# driver_board_v1.net
KiCad netlist of a schematic drawn in EAGLE
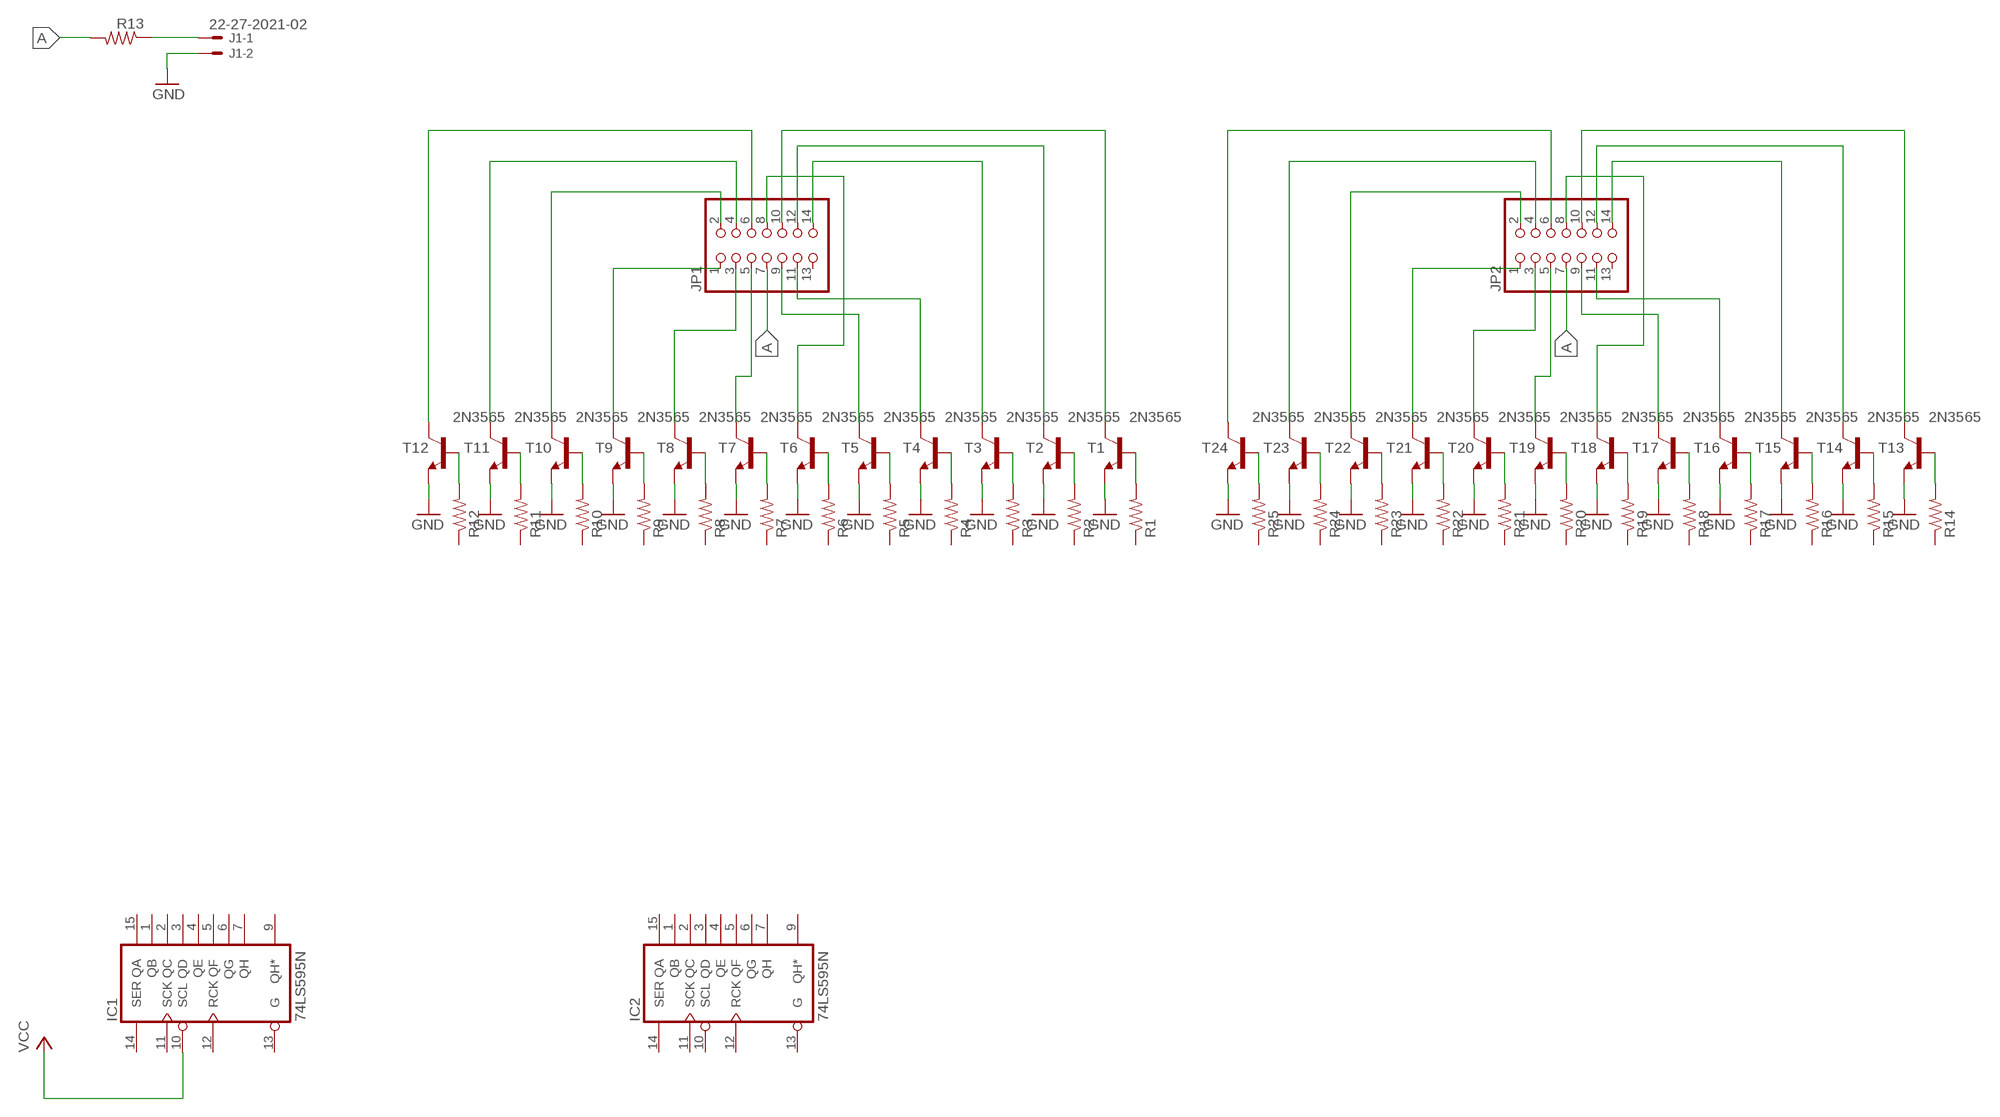
[diagram p0: schematic, sheet 1]

(export (version "E")
  (design (tool "Eeschema 10.0.6"))
  (components
    (comp (ref "IC1")
      (value "74LS595N")
      (footprint "eagle-import:DIL16")
      (libsource (lib "eagle-import") (part "74595NLS"))
    )
    (comp (ref "IC2")
      (value "74LS595N")
      (footprint "eagle-import:DIL16")
      (libsource (lib "eagle-import") (part "74595NLS"))
    )
    (comp (ref "J1")
      (value "22-27-2021-02")
      (footprint "eagle-import:6410-02")
      (libsource (lib "eagle-import") (part "22-?-0227-2021"))
    )
    (comp (ref "JP1")
      (value "PINHD-2X7")
      (footprint "eagle-import:2X07")
      (libsource (lib "eagle-import") (part "PINHD-2X7"))
    )
    (comp (ref "JP2")
      (value "PINHD-2X7")
      (footprint "eagle-import:2X07")
      (libsource (lib "eagle-import") (part "PINHD-2X7"))
    )
    (comp (ref "R1")
      (value "R-US_0204/7")
      (footprint "eagle-import:0204_7")
      (libsource (lib "eagle-import") (part "R-US_0204/7"))
    )
    (comp (ref "R2")
      (value "R-US_0204/7")
      (footprint "eagle-import:0204_7")
      (libsource (lib "eagle-import") (part "R-US_0204/7"))
    )
    (comp (ref "R3")
      (value "R-US_0204/7")
      (footprint "eagle-import:0204_7")
      (libsource (lib "eagle-import") (part "R-US_0204/7"))
    )
    (comp (ref "R4")
      (value "R-US_0204/7")
      (footprint "eagle-import:0204_7")
      (libsource (lib "eagle-import") (part "R-US_0204/7"))
    )
    (comp (ref "R5")
      (value "R-US_0204/7")
      (footprint "eagle-import:0204_7")
      (libsource (lib "eagle-import") (part "R-US_0204/7"))
    )
    (comp (ref "R6")
      (value "R-US_0204/7")
      (footprint "eagle-import:0204_7")
      (libsource (lib "eagle-import") (part "R-US_0204/7"))
    )
    (comp (ref "R7")
      (value "R-US_0204/7")
      (footprint "eagle-import:0204_7")
      (libsource (lib "eagle-import") (part "R-US_0204/7"))
    )
    (comp (ref "R8")
      (value "R-US_0204/7")
      (footprint "eagle-import:0204_7")
      (libsource (lib "eagle-import") (part "R-US_0204/7"))
    )
    (comp (ref "R9")
      (value "R-US_0204/7")
      (footprint "eagle-import:0204_7")
      (libsource (lib "eagle-import") (part "R-US_0204/7"))
    )
    (comp (ref "R10")
      (value "R-US_0204/7")
      (footprint "eagle-import:0204_7")
      (libsource (lib "eagle-import") (part "R-US_0204/7"))
    )
    (comp (ref "R11")
      (value "R-US_0204/7")
      (footprint "eagle-import:0204_7")
      (libsource (lib "eagle-import") (part "R-US_0204/7"))
    )
    (comp (ref "R12")
      (value "R-US_0204/7")
      (footprint "eagle-import:0204_7")
      (libsource (lib "eagle-import") (part "R-US_0204/7"))
    )
    (comp (ref "R13")
      (value "R-US_0204/7")
      (footprint "eagle-import:0204_7")
      (libsource (lib "eagle-import") (part "R-US_0204/7"))
    )
    (comp (ref "R14")
      (value "R-US_0204/7")
      (footprint "eagle-import:0204_7")
      (libsource (lib "eagle-import") (part "R-US_0204/7"))
    )
    (comp (ref "R15")
      (value "R-US_0204/7")
      (footprint "eagle-import:0204_7")
      (libsource (lib "eagle-import") (part "R-US_0204/7"))
    )
    (comp (ref "R16")
      (value "R-US_0204/7")
      (footprint "eagle-import:0204_7")
      (libsource (lib "eagle-import") (part "R-US_0204/7"))
    )
    (comp (ref "R17")
      (value "R-US_0204/7")
      (footprint "eagle-import:0204_7")
      (libsource (lib "eagle-import") (part "R-US_0204/7"))
    )
    (comp (ref "R18")
      (value "R-US_0204/7")
      (footprint "eagle-import:0204_7")
      (libsource (lib "eagle-import") (part "R-US_0204/7"))
    )
    (comp (ref "R19")
      (value "R-US_0204/7")
      (footprint "eagle-import:0204_7")
      (libsource (lib "eagle-import") (part "R-US_0204/7"))
    )
    (comp (ref "R20")
      (value "R-US_0204/7")
      (footprint "eagle-import:0204_7")
      (libsource (lib "eagle-import") (part "R-US_0204/7"))
    )
    (comp (ref "R21")
      (value "R-US_0204/7")
      (footprint "eagle-import:0204_7")
      (libsource (lib "eagle-import") (part "R-US_0204/7"))
    )
    (comp (ref "R22")
      (value "R-US_0204/7")
      (footprint "eagle-import:0204_7")
      (libsource (lib "eagle-import") (part "R-US_0204/7"))
    )
    (comp (ref "R23")
      (value "R-US_0204/7")
      (footprint "eagle-import:0204_7")
      (libsource (lib "eagle-import") (part "R-US_0204/7"))
    )
    (comp (ref "R24")
      (value "R-US_0204/7")
      (footprint "eagle-import:0204_7")
      (libsource (lib "eagle-import") (part "R-US_0204/7"))
    )
    (comp (ref "R25")
      (value "R-US_0204/7")
      (footprint "eagle-import:0204_7")
      (libsource (lib "eagle-import") (part "R-US_0204/7"))
    )
    (comp (ref "T1")
      (value "2N3565")
      (footprint "eagle-import:TO92")
      (libsource (lib "eagle-import") (part "2N3565"))
    )
    (comp (ref "T2")
      (value "2N3565")
      (footprint "eagle-import:TO92")
      (libsource (lib "eagle-import") (part "2N3565"))
    )
    (comp (ref "T3")
      (value "2N3565")
      (footprint "eagle-import:TO92")
      (libsource (lib "eagle-import") (part "2N3565"))
    )
    (comp (ref "T4")
      (value "2N3565")
      (footprint "eagle-import:TO92")
      (libsource (lib "eagle-import") (part "2N3565"))
    )
    (comp (ref "T5")
      (value "2N3565")
      (footprint "eagle-import:TO92")
      (libsource (lib "eagle-import") (part "2N3565"))
    )
    (comp (ref "T6")
      (value "2N3565")
      (footprint "eagle-import:TO92")
      (libsource (lib "eagle-import") (part "2N3565"))
    )
    (comp (ref "T7")
      (value "2N3565")
      (footprint "eagle-import:TO92")
      (libsource (lib "eagle-import") (part "2N3565"))
    )
    (comp (ref "T8")
      (value "2N3565")
      (footprint "eagle-import:TO92")
      (libsource (lib "eagle-import") (part "2N3565"))
    )
    (comp (ref "T9")
      (value "2N3565")
      (footprint "eagle-import:TO92")
      (libsource (lib "eagle-import") (part "2N3565"))
    )
    (comp (ref "T10")
      (value "2N3565")
      (footprint "eagle-import:TO92")
      (libsource (lib "eagle-import") (part "2N3565"))
    )
    (comp (ref "T11")
      (value "2N3565")
      (footprint "eagle-import:TO92")
      (libsource (lib "eagle-import") (part "2N3565"))
    )
    (comp (ref "T12")
      (value "2N3565")
      (footprint "eagle-import:TO92")
      (libsource (lib "eagle-import") (part "2N3565"))
    )
    (comp (ref "T13")
      (value "2N3565")
      (footprint "eagle-import:TO92")
      (libsource (lib "eagle-import") (part "2N3565"))
    )
    (comp (ref "T14")
      (value "2N3565")
      (footprint "eagle-import:TO92")
      (libsource (lib "eagle-import") (part "2N3565"))
    )
    (comp (ref "T15")
      (value "2N3565")
      (footprint "eagle-import:TO92")
      (libsource (lib "eagle-import") (part "2N3565"))
    )
    (comp (ref "T16")
      (value "2N3565")
      (footprint "eagle-import:TO92")
      (libsource (lib "eagle-import") (part "2N3565"))
    )
    (comp (ref "T17")
      (value "2N3565")
      (footprint "eagle-import:TO92")
      (libsource (lib "eagle-import") (part "2N3565"))
    )
    (comp (ref "T18")
      (value "2N3565")
      (footprint "eagle-import:TO92")
      (libsource (lib "eagle-import") (part "2N3565"))
    )
    (comp (ref "T19")
      (value "2N3565")
      (footprint "eagle-import:TO92")
      (libsource (lib "eagle-import") (part "2N3565"))
    )
    (comp (ref "T20")
      (value "2N3565")
      (footprint "eagle-import:TO92")
      (libsource (lib "eagle-import") (part "2N3565"))
    )
    (comp (ref "T21")
      (value "2N3565")
      (footprint "eagle-import:TO92")
      (libsource (lib "eagle-import") (part "2N3565"))
    )
    (comp (ref "T22")
      (value "2N3565")
      (footprint "eagle-import:TO92")
      (libsource (lib "eagle-import") (part "2N3565"))
    )
    (comp (ref "T23")
      (value "2N3565")
      (footprint "eagle-import:TO92")
      (libsource (lib "eagle-import") (part "2N3565"))
    )
    (comp (ref "T24")
      (value "2N3565")
      (footprint "eagle-import:TO92")
      (libsource (lib "eagle-import") (part "2N3565"))
    )
  )
  (nets
    (net (code "1") (name "A") (class "Default")
      (node (ref "JP1") (pin "7") (pinfunction "7_7") (pintype "passive"))
      (node (ref "JP2") (pin "7") (pinfunction "7_7") (pintype "passive"))
      (node (ref "R13") (pin "2") (pinfunction "2_2") (pintype "passive"))
    )
    (net (code "2") (name "GND") (class "Default")
      (node (ref "J1") (pin "2") (pinfunction "S_2") (pintype "passive"))
      (node (ref "T1") (pin "3") (pinfunction "E_3") (pintype "passive"))
      (node (ref "T10") (pin "3") (pinfunction "E_3") (pintype "passive"))
      (node (ref "T11") (pin "3") (pinfunction "E_3") (pintype "passive"))
      (node (ref "T12") (pin "3") (pinfunction "E_3") (pintype "passive"))
      (node (ref "T13") (pin "3") (pinfunction "E_3") (pintype "passive"))
      (node (ref "T14") (pin "3") (pinfunction "E_3") (pintype "passive"))
      (node (ref "T15") (pin "3") (pinfunction "E_3") (pintype "passive"))
      (node (ref "T16") (pin "3") (pinfunction "E_3") (pintype "passive"))
      (node (ref "T17") (pin "3") (pinfunction "E_3") (pintype "passive"))
      (node (ref "T18") (pin "3") (pinfunction "E_3") (pintype "passive"))
      (node (ref "T19") (pin "3") (pinfunction "E_3") (pintype "passive"))
      (node (ref "T2") (pin "3") (pinfunction "E_3") (pintype "passive"))
      (node (ref "T20") (pin "3") (pinfunction "E_3") (pintype "passive"))
      (node (ref "T21") (pin "3") (pinfunction "E_3") (pintype "passive"))
      (node (ref "T22") (pin "3") (pinfunction "E_3") (pintype "passive"))
      (node (ref "T23") (pin "3") (pinfunction "E_3") (pintype "passive"))
      (node (ref "T24") (pin "3") (pinfunction "E_3") (pintype "passive"))
      (node (ref "T3") (pin "3") (pinfunction "E_3") (pintype "passive"))
      (node (ref "T4") (pin "3") (pinfunction "E_3") (pintype "passive"))
      (node (ref "T5") (pin "3") (pinfunction "E_3") (pintype "passive"))
      (node (ref "T6") (pin "3") (pinfunction "E_3") (pintype "passive"))
      (node (ref "T7") (pin "3") (pinfunction "E_3") (pintype "passive"))
      (node (ref "T8") (pin "3") (pinfunction "E_3") (pintype "passive"))
      (node (ref "T9") (pin "3") (pinfunction "E_3") (pintype "passive"))
    )
    (net (code "3") (name "Net-(J1A-S)") (class "Default")
      (node (ref "J1") (pin "1") (pinfunction "S_1") (pintype "passive"))
      (node (ref "R13") (pin "1") (pinfunction "1_1") (pintype "passive"))
    )
    (net (code "4") (name "Net-(T1-B)") (class "Default")
      (node (ref "R1") (pin "2") (pinfunction "2_2") (pintype "passive"))
      (node (ref "T1") (pin "2") (pinfunction "B_2") (pintype "passive"))
    )
    (net (code "5") (name "Net-(T1-C)") (class "Default")
      (node (ref "JP1") (pin "10") (pinfunction "10_10") (pintype "passive"))
      (node (ref "T1") (pin "1") (pinfunction "C_1") (pintype "passive"))
    )
    (net (code "6") (name "Net-(T2-B)") (class "Default")
      (node (ref "R2") (pin "2") (pinfunction "2_2") (pintype "passive"))
      (node (ref "T2") (pin "2") (pinfunction "B_2") (pintype "passive"))
    )
    (net (code "7") (name "Net-(T2-C)") (class "Default")
      (node (ref "JP1") (pin "12") (pinfunction "12_12") (pintype "passive"))
      (node (ref "T2") (pin "1") (pinfunction "C_1") (pintype "passive"))
    )
    (net (code "8") (name "Net-(T3-B)") (class "Default")
      (node (ref "R3") (pin "2") (pinfunction "2_2") (pintype "passive"))
      (node (ref "T3") (pin "2") (pinfunction "B_2") (pintype "passive"))
    )
    (net (code "9") (name "Net-(T3-C)") (class "Default")
      (node (ref "JP1") (pin "14") (pinfunction "14_14") (pintype "passive"))
      (node (ref "T3") (pin "1") (pinfunction "C_1") (pintype "passive"))
    )
    (net (code "10") (name "Net-(T4-B)") (class "Default")
      (node (ref "R4") (pin "2") (pinfunction "2_2") (pintype "passive"))
      (node (ref "T4") (pin "2") (pinfunction "B_2") (pintype "passive"))
    )
    (net (code "11") (name "Net-(T4-C)") (class "Default")
      (node (ref "JP1") (pin "11") (pinfunction "11_11") (pintype "passive"))
      (node (ref "T4") (pin "1") (pinfunction "C_1") (pintype "passive"))
    )
    (net (code "12") (name "Net-(T5-B)") (class "Default")
      (node (ref "R5") (pin "2") (pinfunction "2_2") (pintype "passive"))
      (node (ref "T5") (pin "2") (pinfunction "B_2") (pintype "passive"))
    )
    (net (code "13") (name "Net-(T5-C)") (class "Default")
      (node (ref "JP1") (pin "9") (pinfunction "9_9") (pintype "passive"))
      (node (ref "T5") (pin "1") (pinfunction "C_1") (pintype "passive"))
    )
    (net (code "14") (name "Net-(T6-B)") (class "Default")
      (node (ref "R6") (pin "2") (pinfunction "2_2") (pintype "passive"))
      (node (ref "T6") (pin "2") (pinfunction "B_2") (pintype "passive"))
    )
    (net (code "15") (name "Net-(T6-C)") (class "Default")
      (node (ref "JP1") (pin "8") (pinfunction "8_8") (pintype "passive"))
      (node (ref "T6") (pin "1") (pinfunction "C_1") (pintype "passive"))
    )
    (net (code "16") (name "Net-(T7-B)") (class "Default")
      (node (ref "R7") (pin "2") (pinfunction "2_2") (pintype "passive"))
      (node (ref "T7") (pin "2") (pinfunction "B_2") (pintype "passive"))
    )
    (net (code "17") (name "Net-(T7-C)") (class "Default")
      (node (ref "JP1") (pin "5") (pinfunction "5_5") (pintype "passive"))
      (node (ref "T7") (pin "1") (pinfunction "C_1") (pintype "passive"))
    )
    (net (code "18") (name "Net-(T8-B)") (class "Default")
      (node (ref "R8") (pin "2") (pinfunction "2_2") (pintype "passive"))
      (node (ref "T8") (pin "2") (pinfunction "B_2") (pintype "passive"))
    )
    (net (code "19") (name "Net-(T8-C)") (class "Default")
      (node (ref "JP1") (pin "3") (pinfunction "3_3") (pintype "passive"))
      (node (ref "T8") (pin "1") (pinfunction "C_1") (pintype "passive"))
    )
    (net (code "20") (name "Net-(T9-B)") (class "Default")
      (node (ref "R9") (pin "2") (pinfunction "2_2") (pintype "passive"))
      (node (ref "T9") (pin "2") (pinfunction "B_2") (pintype "passive"))
    )
    (net (code "21") (name "Net-(T9-C)") (class "Default")
      (node (ref "JP1") (pin "1") (pinfunction "1_1") (pintype "passive"))
      (node (ref "T9") (pin "1") (pinfunction "C_1") (pintype "passive"))
    )
    (net (code "22") (name "Net-(T10-B)") (class "Default")
      (node (ref "R10") (pin "2") (pinfunction "2_2") (pintype "passive"))
      (node (ref "T10") (pin "2") (pinfunction "B_2") (pintype "passive"))
    )
    (net (code "23") (name "Net-(T10-C)") (class "Default")
      (node (ref "JP1") (pin "2") (pinfunction "2_2") (pintype "passive"))
      (node (ref "T10") (pin "1") (pinfunction "C_1") (pintype "passive"))
    )
    (net (code "24") (name "Net-(T11-B)") (class "Default")
      (node (ref "R11") (pin "2") (pinfunction "2_2") (pintype "passive"))
      (node (ref "T11") (pin "2") (pinfunction "B_2") (pintype "passive"))
    )
    (net (code "25") (name "Net-(T11-C)") (class "Default")
      (node (ref "JP1") (pin "4") (pinfunction "4_4") (pintype "passive"))
      (node (ref "T11") (pin "1") (pinfunction "C_1") (pintype "passive"))
    )
    (net (code "26") (name "Net-(T12-B)") (class "Default")
      (node (ref "R12") (pin "2") (pinfunction "2_2") (pintype "passive"))
      (node (ref "T12") (pin "2") (pinfunction "B_2") (pintype "passive"))
    )
    (net (code "27") (name "Net-(T12-C)") (class "Default")
      (node (ref "JP1") (pin "6") (pinfunction "6_6") (pintype "passive"))
      (node (ref "T12") (pin "1") (pinfunction "C_1") (pintype "passive"))
    )
    (net (code "28") (name "Net-(T13-B)") (class "Default")
      (node (ref "R14") (pin "2") (pinfunction "2_2") (pintype "passive"))
      (node (ref "T13") (pin "2") (pinfunction "B_2") (pintype "passive"))
    )
    (net (code "29") (name "Net-(T13-C)") (class "Default")
      (node (ref "JP2") (pin "10") (pinfunction "10_10") (pintype "passive"))
      (node (ref "T13") (pin "1") (pinfunction "C_1") (pintype "passive"))
    )
    (net (code "30") (name "Net-(T14-B)") (class "Default")
      (node (ref "R15") (pin "2") (pinfunction "2_2") (pintype "passive"))
      (node (ref "T14") (pin "2") (pinfunction "B_2") (pintype "passive"))
    )
    (net (code "31") (name "Net-(T14-C)") (class "Default")
      (node (ref "JP2") (pin "12") (pinfunction "12_12") (pintype "passive"))
      (node (ref "T14") (pin "1") (pinfunction "C_1") (pintype "passive"))
    )
    (net (code "32") (name "Net-(T15-B)") (class "Default")
      (node (ref "R16") (pin "2") (pinfunction "2_2") (pintype "passive"))
      (node (ref "T15") (pin "2") (pinfunction "B_2") (pintype "passive"))
    )
    (net (code "33") (name "Net-(T15-C)") (class "Default")
      (node (ref "JP2") (pin "14") (pinfunction "14_14") (pintype "passive"))
      (node (ref "T15") (pin "1") (pinfunction "C_1") (pintype "passive"))
    )
    (net (code "34") (name "Net-(T16-B)") (class "Default")
      (node (ref "R17") (pin "2") (pinfunction "2_2") (pintype "passive"))
      (node (ref "T16") (pin "2") (pinfunction "B_2") (pintype "passive"))
    )
    (net (code "35") (name "Net-(T16-C)") (class "Default")
      (node (ref "JP2") (pin "11") (pinfunction "11_11") (pintype "passive"))
      (node (ref "T16") (pin "1") (pinfunction "C_1") (pintype "passive"))
    )
    (net (code "36") (name "Net-(T17-B)") (class "Default")
      (node (ref "R18") (pin "2") (pinfunction "2_2") (pintype "passive"))
      (node (ref "T17") (pin "2") (pinfunction "B_2") (pintype "passive"))
    )
    (net (code "37") (name "Net-(T17-C)") (class "Default")
      (node (ref "JP2") (pin "9") (pinfunction "9_9") (pintype "passive"))
      (node (ref "T17") (pin "1") (pinfunction "C_1") (pintype "passive"))
    )
    (net (code "38") (name "Net-(T18-B)") (class "Default")
      (node (ref "R19") (pin "2") (pinfunction "2_2") (pintype "passive"))
      (node (ref "T18") (pin "2") (pinfunction "B_2") (pintype "passive"))
    )
    (net (code "39") (name "Net-(T18-C)") (class "Default")
      (node (ref "JP2") (pin "8") (pinfunction "8_8") (pintype "passive"))
      (node (ref "T18") (pin "1") (pinfunction "C_1") (pintype "passive"))
    )
    (net (code "40") (name "Net-(T19-B)") (class "Default")
      (node (ref "R20") (pin "2") (pinfunction "2_2") (pintype "passive"))
      (node (ref "T19") (pin "2") (pinfunction "B_2") (pintype "passive"))
    )
    (net (code "41") (name "Net-(T19-C)") (class "Default")
      (node (ref "JP2") (pin "5") (pinfunction "5_5") (pintype "passive"))
      (node (ref "T19") (pin "1") (pinfunction "C_1") (pintype "passive"))
    )
    (net (code "42") (name "Net-(T20-B)") (class "Default")
      (node (ref "R21") (pin "2") (pinfunction "2_2") (pintype "passive"))
      (node (ref "T20") (pin "2") (pinfunction "B_2") (pintype "passive"))
    )
    (net (code "43") (name "Net-(T20-C)") (class "Default")
      (node (ref "JP2") (pin "3") (pinfunction "3_3") (pintype "passive"))
      (node (ref "T20") (pin "1") (pinfunction "C_1") (pintype "passive"))
    )
    (net (code "44") (name "Net-(T21-B)") (class "Default")
      (node (ref "R22") (pin "2") (pinfunction "2_2") (pintype "passive"))
      (node (ref "T21") (pin "2") (pinfunction "B_2") (pintype "passive"))
    )
    (net (code "45") (name "Net-(T21-C)") (class "Default")
      (node (ref "JP2") (pin "1") (pinfunction "1_1") (pintype "passive"))
      (node (ref "T21") (pin "1") (pinfunction "C_1") (pintype "passive"))
    )
    (net (code "46") (name "Net-(T22-B)") (class "Default")
      (node (ref "R23") (pin "2") (pinfunction "2_2") (pintype "passive"))
      (node (ref "T22") (pin "2") (pinfunction "B_2") (pintype "passive"))
    )
    (net (code "47") (name "Net-(T22-C)") (class "Default")
      (node (ref "JP2") (pin "2") (pinfunction "2_2") (pintype "passive"))
      (node (ref "T22") (pin "1") (pinfunction "C_1") (pintype "passive"))
    )
    (net (code "48") (name "Net-(T23-B)") (class "Default")
      (node (ref "R24") (pin "2") (pinfunction "2_2") (pintype "passive"))
      (node (ref "T23") (pin "2") (pinfunction "B_2") (pintype "passive"))
    )
    (net (code "49") (name "Net-(T23-C)") (class "Default")
      (node (ref "JP2") (pin "4") (pinfunction "4_4") (pintype "passive"))
      (node (ref "T23") (pin "1") (pinfunction "C_1") (pintype "passive"))
    )
    (net (code "50") (name "Net-(T24-B)") (class "Default")
      (node (ref "R25") (pin "2") (pinfunction "2_2") (pintype "passive"))
      (node (ref "T24") (pin "2") (pinfunction "B_2") (pintype "passive"))
    )
    (net (code "51") (name "Net-(T24-C)") (class "Default")
      (node (ref "JP2") (pin "6") (pinfunction "6_6") (pintype "passive"))
      (node (ref "T24") (pin "1") (pinfunction "C_1") (pintype "passive"))
    )
    (net (code "52") (name "VCC") (class "Default")
      (node (ref "IC1") (pin "10") (pinfunction "SCL_10") (pintype "input"))
    )
    (net (code "53") (name "unconnected-(IC1A-G-Pad13)") (class "Default")
      (node (ref "IC1") (pin "13") (pinfunction "G_13") (pintype "input"))
    )
    (net (code "54") (name "unconnected-(IC1A-QA-Pad15)") (class "Default")
      (node (ref "IC1") (pin "15") (pinfunction "QA_15") (pintype "tri_state"))
    )
    (net (code "55") (name "unconnected-(IC1A-QB-Pad1)") (class "Default")
      (node (ref "IC1") (pin "1") (pinfunction "QB_1") (pintype "tri_state"))
    )
    (net (code "56") (name "unconnected-(IC1A-QC-Pad2)") (class "Default")
      (node (ref "IC1") (pin "2") (pinfunction "QC_2") (pintype "tri_state"))
    )
    (net (code "57") (name "unconnected-(IC1A-QD-Pad3)") (class "Default")
      (node (ref "IC1") (pin "3") (pinfunction "QD_3") (pintype "tri_state"))
    )
    (net (code "58") (name "unconnected-(IC1A-QE-Pad4)") (class "Default")
      (node (ref "IC1") (pin "4") (pinfunction "QE_4") (pintype "tri_state"))
    )
    (net (code "59") (name "unconnected-(IC1A-QF-Pad5)") (class "Default")
      (node (ref "IC1") (pin "5") (pinfunction "QF_5") (pintype "tri_state"))
    )
    (net (code "60") (name "unconnected-(IC1A-QG-Pad6)") (class "Default")
      (node (ref "IC1") (pin "6") (pinfunction "QG_6") (pintype "tri_state"))
    )
    (net (code "61") (name "unconnected-(IC1A-QH*-Pad9)") (class "Default")
      (node (ref "IC1") (pin "9") (pinfunction "QH*_9") (pintype "tri_state"))
    )
    (net (code "62") (name "unconnected-(IC1A-QH-Pad7)") (class "Default")
      (node (ref "IC1") (pin "7") (pinfunction "QH_7") (pintype "tri_state"))
    )
    (net (code "63") (name "unconnected-(IC1A-RCK-Pad12)") (class "Default")
      (node (ref "IC1") (pin "12") (pinfunction "RCK_12") (pintype "input"))
    )
    (net (code "64") (name "unconnected-(IC1A-SCK-Pad11)") (class "Default")
      (node (ref "IC1") (pin "11") (pinfunction "SCK_11") (pintype "input"))
    )
    (net (code "65") (name "unconnected-(IC1A-SER-Pad14)") (class "Default")
      (node (ref "IC1") (pin "14") (pinfunction "SER_14") (pintype "input"))
    )
    (net (code "66") (name "unconnected-(IC2A-G-Pad13)") (class "Default")
      (node (ref "IC2") (pin "13") (pinfunction "G_13") (pintype "input"))
    )
    (net (code "67") (name "unconnected-(IC2A-QA-Pad15)") (class "Default")
      (node (ref "IC2") (pin "15") (pinfunction "QA_15") (pintype "tri_state"))
    )
    (net (code "68") (name "unconnected-(IC2A-QB-Pad1)") (class "Default")
      (node (ref "IC2") (pin "1") (pinfunction "QB_1") (pintype "tri_state"))
    )
    (net (code "69") (name "unconnected-(IC2A-QC-Pad2)") (class "Default")
      (node (ref "IC2") (pin "2") (pinfunction "QC_2") (pintype "tri_state"))
    )
    (net (code "70") (name "unconnected-(IC2A-QD-Pad3)") (class "Default")
      (node (ref "IC2") (pin "3") (pinfunction "QD_3") (pintype "tri_state"))
    )
    (net (code "71") (name "unconnected-(IC2A-QE-Pad4)") (class "Default")
      (node (ref "IC2") (pin "4") (pinfunction "QE_4") (pintype "tri_state"))
    )
    (net (code "72") (name "unconnected-(IC2A-QF-Pad5)") (class "Default")
      (node (ref "IC2") (pin "5") (pinfunction "QF_5") (pintype "tri_state"))
    )
    (net (code "73") (name "unconnected-(IC2A-QG-Pad6)") (class "Default")
      (node (ref "IC2") (pin "6") (pinfunction "QG_6") (pintype "tri_state"))
    )
    (net (code "74") (name "unconnected-(IC2A-QH*-Pad9)") (class "Default")
      (node (ref "IC2") (pin "9") (pinfunction "QH*_9") (pintype "tri_state"))
    )
    (net (code "75") (name "unconnected-(IC2A-QH-Pad7)") (class "Default")
      (node (ref "IC2") (pin "7") (pinfunction "QH_7") (pintype "tri_state"))
    )
    (net (code "76") (name "unconnected-(IC2A-RCK-Pad12)") (class "Default")
      (node (ref "IC2") (pin "12") (pinfunction "RCK_12") (pintype "input"))
    )
    (net (code "77") (name "unconnected-(IC2A-SCK-Pad11)") (class "Default")
      (node (ref "IC2") (pin "11") (pinfunction "SCK_11") (pintype "input"))
    )
    (net (code "78") (name "unconnected-(IC2A-SCL-Pad10)") (class "Default")
      (node (ref "IC2") (pin "10") (pinfunction "SCL_10") (pintype "input"))
    )
    (net (code "79") (name "unconnected-(IC2A-SER-Pad14)") (class "Default")
      (node (ref "IC2") (pin "14") (pinfunction "SER_14") (pintype "input"))
    )
    (net (code "80") (name "unconnected-(JP1-Pad13)") (class "Default")
      (node (ref "JP1") (pin "13") (pinfunction "13_13") (pintype "passive"))
    )
    (net (code "81") (name "unconnected-(JP2-Pad13)") (class "Default")
      (node (ref "JP2") (pin "13") (pinfunction "13_13") (pintype "passive"))
    )
    (net (code "82") (name "unconnected-(R1-Pad1)") (class "Default")
      (node (ref "R1") (pin "1") (pinfunction "1_1") (pintype "passive"))
    )
    (net (code "83") (name "unconnected-(R2-Pad1)") (class "Default")
      (node (ref "R2") (pin "1") (pinfunction "1_1") (pintype "passive"))
    )
    (net (code "84") (name "unconnected-(R3-Pad1)") (class "Default")
      (node (ref "R3") (pin "1") (pinfunction "1_1") (pintype "passive"))
    )
    (net (code "85") (name "unconnected-(R4-Pad1)") (class "Default")
      (node (ref "R4") (pin "1") (pinfunction "1_1") (pintype "passive"))
    )
    (net (code "86") (name "unconnected-(R5-Pad1)") (class "Default")
      (node (ref "R5") (pin "1") (pinfunction "1_1") (pintype "passive"))
    )
    (net (code "87") (name "unconnected-(R6-Pad1)") (class "Default")
      (node (ref "R6") (pin "1") (pinfunction "1_1") (pintype "passive"))
    )
    (net (code "88") (name "unconnected-(R7-Pad1)") (class "Default")
      (node (ref "R7") (pin "1") (pinfunction "1_1") (pintype "passive"))
    )
    (net (code "89") (name "unconnected-(R8-Pad1)") (class "Default")
      (node (ref "R8") (pin "1") (pinfunction "1_1") (pintype "passive"))
    )
    (net (code "90") (name "unconnected-(R9-Pad1)") (class "Default")
      (node (ref "R9") (pin "1") (pinfunction "1_1") (pintype "passive"))
    )
    (net (code "91") (name "unconnected-(R10-Pad1)") (class "Default")
      (node (ref "R10") (pin "1") (pinfunction "1_1") (pintype "passive"))
    )
    (net (code "92") (name "unconnected-(R11-Pad1)") (class "Default")
      (node (ref "R11") (pin "1") (pinfunction "1_1") (pintype "passive"))
    )
    (net (code "93") (name "unconnected-(R12-Pad1)") (class "Default")
      (node (ref "R12") (pin "1") (pinfunction "1_1") (pintype "passive"))
    )
    (net (code "94") (name "unconnected-(R14-Pad1)") (class "Default")
      (node (ref "R14") (pin "1") (pinfunction "1_1") (pintype "passive"))
    )
    (net (code "95") (name "unconnected-(R15-Pad1)") (class "Default")
      (node (ref "R15") (pin "1") (pinfunction "1_1") (pintype "passive"))
    )
    (net (code "96") (name "unconnected-(R16-Pad1)") (class "Default")
      (node (ref "R16") (pin "1") (pinfunction "1_1") (pintype "passive"))
    )
    (net (code "97") (name "unconnected-(R17-Pad1)") (class "Default")
      (node (ref "R17") (pin "1") (pinfunction "1_1") (pintype "passive"))
    )
    (net (code "98") (name "unconnected-(R18-Pad1)") (class "Default")
      (node (ref "R18") (pin "1") (pinfunction "1_1") (pintype "passive"))
    )
    (net (code "99") (name "unconnected-(R19-Pad1)") (class "Default")
      (node (ref "R19") (pin "1") (pinfunction "1_1") (pintype "passive"))
    )
    (net (code "100") (name "unconnected-(R20-Pad1)") (class "Default")
      (node (ref "R20") (pin "1") (pinfunction "1_1") (pintype "passive"))
    )
    (net (code "101") (name "unconnected-(R21-Pad1)") (class "Default")
      (node (ref "R21") (pin "1") (pinfunction "1_1") (pintype "passive"))
    )
    (net (code "102") (name "unconnected-(R22-Pad1)") (class "Default")
      (node (ref "R22") (pin "1") (pinfunction "1_1") (pintype "passive"))
    )
    (net (code "103") (name "unconnected-(R23-Pad1)") (class "Default")
      (node (ref "R23") (pin "1") (pinfunction "1_1") (pintype "passive"))
    )
    (net (code "104") (name "unconnected-(R24-Pad1)") (class "Default")
      (node (ref "R24") (pin "1") (pinfunction "1_1") (pintype "passive"))
    )
    (net (code "105") (name "unconnected-(R25-Pad1)") (class "Default")
      (node (ref "R25") (pin "1") (pinfunction "1_1") (pintype "passive"))
    )
  )
)
